# SimplePayload.net
KiCad netlist of a schematic drawn in EAGLE
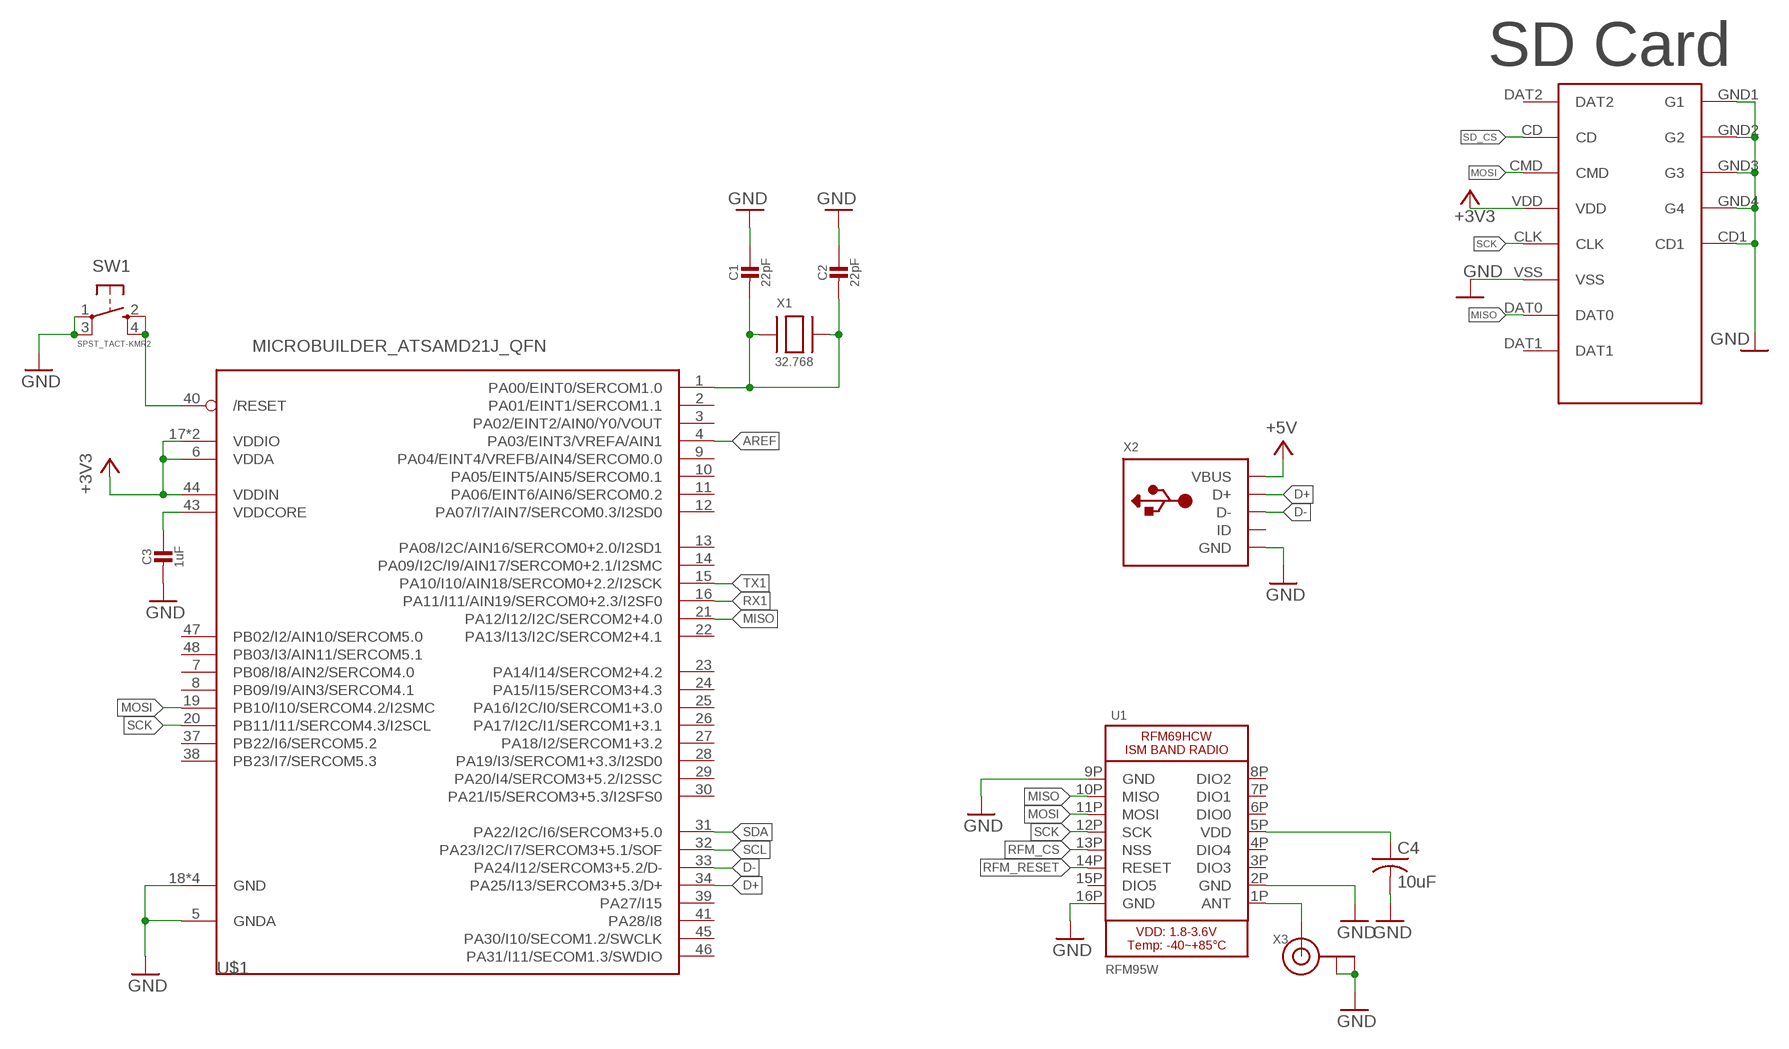
[diagram p0: schematic, sheet 1]

(export (version "E")
  (design (tool "Eeschema 10.0.6"))
  (components
    (comp (ref "C1")
      (value "22pF")
      (footprint "eagle-import:MICROBUILDER_0603-NO")
      (libsource (lib "eagle-import") (part "MICROBUILDER_CAP_CERAMIC0603_NO"))
    )
    (comp (ref "C2")
      (value "22pF")
      (footprint "eagle-import:MICROBUILDER_0603-NO")
      (libsource (lib "eagle-import") (part "MICROBUILDER_CAP_CERAMIC0603_NO"))
    )
    (comp (ref "C3")
      (value "1uF")
      (footprint "eagle-import:MICROBUILDER_0603-NO")
      (libsource (lib "eagle-import") (part "MICROBUILDER_CAP_CERAMIC0603_NO"))
    )
    (comp (ref "C4")
      (value "10uF")
      (footprint "eagle-import:C0805")
      (libsource (lib "eagle-import") (part "C-USC0805"))
    )
    (comp (ref "SW1")
      (value "SPST_TACT-KMR2")
      (footprint "eagle-import:KMR2")
      (libsource (lib "eagle-import") (part "SPST_TACT-KMR2"))
    )
    (comp (ref "U$1")
      (value "MICROBUILDER_ATSAMD21J_QFN")
      (footprint "eagle-import:MICROBUILDER_TQFN48_7MM")
      (libsource (lib "eagle-import") (part "MICROBUILDER_ATSAMD21J_QFN"))
    )
    (comp (ref "U$4")
      (value "MICRO_SD")
      (footprint "eagle-import:MICRO_SD_HINGED")
      (libsource (lib "eagle-import") (part "MICRO_SD"))
    )
    (comp (ref "U1")
      (value "RFM95W")
      (footprint "eagle-import:MICROBUILDER_RFMHCW_SMT")
      (libsource (lib "eagle-import") (part "MICROBUILDER_RFM69HCW_SMT"))
    )
    (comp (ref "X1")
      (value "32.768")
      (footprint "eagle-import:ADAFRUIT2_XTAL3215")
      (libsource (lib "eagle-import") (part "ADAFRUIT2_XTAL-3.2X1.5"))
    )
    (comp (ref "X2")
      (value "MICROBUILDER_USB_MICRO_20329_V2")
      (footprint "eagle-import:MICROBUILDER_4UCONN_20329_V2")
      (libsource (lib "eagle-import") (part "MICROBUILDER_USB_MICRO_20329_V2"))
    )
    (comp (ref "X3")
      (value "MICROBUILDER_ANTENNA_U.FL")
      (footprint "eagle-import:MICROBUILDER_U.FL")
      (libsource (lib "eagle-import") (part "MICROBUILDER_ANTENNA_U.FL"))
    )
  )
  (nets
    (net (code "1") (name "+3V3") (class "Default")
      (node (ref "U$1") (pin "17") (pinfunction "VDDIO_17") (pintype "power_in"))
      (node (ref "U$1") (pin "36") (pinfunction "VDDIO_36") (pintype "power_in"))
      (node (ref "U$1") (pin "44") (pinfunction "VDDIN_44") (pintype "power_in"))
      (node (ref "U$1") (pin "6") (pinfunction "VDDA_6") (pintype "power_in"))
      (node (ref "U$4") (pin "VDD") (pinfunction "VDD_VDD") (pintype "bidirectional"))
    )
    (net (code "2") (name "+5V") (class "Default")
      (node (ref "X2") (pin "VBUS") (pinfunction "VBUS_VBUS") (pintype "power_in"))
    )
    (net (code "3") (name "AREF") (class "Default")
      (node (ref "U$1") (pin "4") (pinfunction "PA03/EINT3/VREFA/AIN1_4") (pintype "bidirectional"))
    )
    (net (code "4") (name "D+") (class "Default")
      (node (ref "U$1") (pin "34") (pinfunction "PA25/I13/SERCOM3+5.3/D+_34") (pintype "bidirectional"))
      (node (ref "X2") (pin "D+") (pinfunction "D+_D+") (pintype "bidirectional"))
    )
    (net (code "5") (name "D-") (class "Default")
      (node (ref "U$1") (pin "33") (pinfunction "PA24/I12/SERCOM3+5.2/D-_33") (pintype "bidirectional"))
      (node (ref "X2") (pin "D-") (pinfunction "D-_D-") (pintype "bidirectional"))
    )
    (net (code "6") (name "GND") (class "Default")
      (node (ref "C1") (pin "1") (pinfunction "1_1") (pintype "passive"))
      (node (ref "C2") (pin "1") (pinfunction "1_1") (pintype "passive"))
      (node (ref "C3") (pin "2") (pinfunction "2_2") (pintype "passive"))
      (node (ref "C4") (pin "2") (pinfunction "2_2") (pintype "passive"))
      (node (ref "SW1") (pin "1") (pinfunction "P_1") (pintype "passive"))
      (node (ref "SW1") (pin "3") (pinfunction "P1_3") (pintype "passive"))
      (node (ref "U$1") (pin "18") (pinfunction "GND_18") (pintype "power_in"))
      (node (ref "U$1") (pin "35") (pinfunction "GND_35") (pintype "power_in"))
      (node (ref "U$1") (pin "42") (pinfunction "GND_42") (pintype "power_in"))
      (node (ref "U$1") (pin "5") (pinfunction "GNDA_5") (pintype "power_in"))
      (node (ref "U$1") (pin "THERMAL") (pinfunction "GND_THERMAL") (pintype "power_in"))
      (node (ref "U$4") (pin "CD1") (pinfunction "CD1_CD1") (pintype "bidirectional"))
      (node (ref "U$4") (pin "GND1") (pinfunction "G1_GND1") (pintype "bidirectional"))
      (node (ref "U$4") (pin "GND2") (pinfunction "G2_GND2") (pintype "bidirectional"))
      (node (ref "U$4") (pin "GND3") (pinfunction "G3_GND3") (pintype "bidirectional"))
      (node (ref "U$4") (pin "GND4") (pinfunction "G4_GND4") (pintype "bidirectional"))
      (node (ref "U$4") (pin "VSS") (pinfunction "VSS_VSS") (pintype "bidirectional"))
      (node (ref "U1") (pin "16P") (pinfunction "GND_16P") (pintype "power_in"))
      (node (ref "U1") (pin "2P") (pinfunction "GND_2P") (pintype "power_in"))
      (node (ref "U1") (pin "9P") (pinfunction "GND_9P") (pintype "power_in"))
      (node (ref "X2") (pin "BASE@1") (pinfunction "GND_BASE@1") (pintype "power_in"))
      (node (ref "X2") (pin "BASE@2") (pinfunction "GND_BASE@2") (pintype "power_in"))
      (node (ref "X2") (pin "GND") (pinfunction "GND_GND") (pintype "power_in"))
      (node (ref "X2") (pin "SPRT@1") (pinfunction "GND_SPRT@1") (pintype "power_in"))
      (node (ref "X2") (pin "SPRT@2") (pinfunction "GND_SPRT@2") (pintype "power_in"))
      (node (ref "X2") (pin "SPRT@3") (pinfunction "GND_SPRT@3") (pintype "power_in"))
      (node (ref "X2") (pin "SPRT@4") (pinfunction "GND_SPRT@4") (pintype "power_in"))
      (node (ref "X3") (pin "1") (pinfunction "GND_1") (pintype "passive"))
      (node (ref "X3") (pin "2") (pinfunction "GND_2") (pintype "passive"))
    )
    (net (code "7") (name "MISO") (class "Default")
      (node (ref "U$1") (pin "21") (pinfunction "PA12/I12/I2C/SERCOM2+4.0_21") (pintype "bidirectional"))
      (node (ref "U$4") (pin "DAT0") (pinfunction "DAT0_DAT0") (pintype "bidirectional"))
      (node (ref "U1") (pin "10P") (pinfunction "MISO_10P") (pintype "output"))
    )
    (net (code "8") (name "MOSI") (class "Default")
      (node (ref "U$1") (pin "19") (pinfunction "PB10/I10/SERCOM4.2/I2SMC_19") (pintype "bidirectional"))
      (node (ref "U$4") (pin "CMD") (pinfunction "CMD_CMD") (pintype "bidirectional"))
      (node (ref "U1") (pin "11P") (pinfunction "MOSI_11P") (pintype "input"))
    )
    (net (code "9") (name "Net-(SW1-S)") (class "Default")
      (node (ref "SW1") (pin "2") (pinfunction "S_2") (pintype "passive"))
      (node (ref "SW1") (pin "4") (pinfunction "S1_4") (pintype "passive"))
      (node (ref "U$1") (pin "40") (pinfunction "/RESET_40") (pintype "bidirectional"))
    )
    (net (code "10") (name "Net-(U$1-PA00{slash}EINT0{slash}SERCOM1.0)") (class "Default")
      (node (ref "C1") (pin "2") (pinfunction "2_2") (pintype "passive"))
      (node (ref "C2") (pin "2") (pinfunction "2_2") (pintype "passive"))
      (node (ref "U$1") (pin "1") (pinfunction "PA00/EINT0/SERCOM1.0_1") (pintype "bidirectional"))
      (node (ref "X1") (pin "P$1") (pinfunction "P$1_P$1") (pintype "bidirectional"))
      (node (ref "X1") (pin "P$2") (pinfunction "P$2_P$2") (pintype "bidirectional"))
    )
    (net (code "11") (name "Net-(U$1-VDDCORE)") (class "Default")
      (node (ref "C3") (pin "1") (pinfunction "1_1") (pintype "passive"))
      (node (ref "U$1") (pin "43") (pinfunction "VDDCORE_43") (pintype "power_in"))
    )
    (net (code "12") (name "Net-(U1-ANT)") (class "Default")
      (node (ref "U1") (pin "1P") (pinfunction "ANT_1P") (pintype "bidirectional"))
      (node (ref "X3") (pin "3") (pinfunction "SIGNAL_3") (pintype "passive"))
    )
    (net (code "13") (name "Net-(U1-VDD)") (class "Default")
      (node (ref "C4") (pin "1") (pinfunction "1_1") (pintype "passive"))
      (node (ref "U1") (pin "5P") (pinfunction "VDD_5P") (pintype "power_in"))
    )
    (net (code "14") (name "RFM_CS") (class "Default")
      (node (ref "U1") (pin "13P") (pinfunction "NSS_13P") (pintype "input"))
    )
    (net (code "15") (name "RFM_RESET") (class "Default")
      (node (ref "U1") (pin "14P") (pinfunction "RESET_14P") (pintype "input"))
    )
    (net (code "16") (name "RX1") (class "Default")
      (node (ref "U$1") (pin "16") (pinfunction "PA11/I11/AIN19/SERCOM0+2.3/I2SF0_16") (pintype "bidirectional"))
    )
    (net (code "17") (name "SCK") (class "Default")
      (node (ref "U$1") (pin "20") (pinfunction "PB11/I11/SERCOM4.3/I2SCL_20") (pintype "bidirectional"))
      (node (ref "U$4") (pin "CLK") (pinfunction "CLK_CLK") (pintype "bidirectional"))
      (node (ref "U1") (pin "12P") (pinfunction "SCK_12P") (pintype "input"))
    )
    (net (code "18") (name "SCL") (class "Default")
      (node (ref "U$1") (pin "32") (pinfunction "PA23/I2C/I7/SERCOM3+5.1/SOF_32") (pintype "bidirectional"))
    )
    (net (code "19") (name "SDA") (class "Default")
      (node (ref "U$1") (pin "31") (pinfunction "PA22/I2C/I6/SERCOM3+5.0_31") (pintype "bidirectional"))
    )
    (net (code "20") (name "SD_CS") (class "Default")
      (node (ref "U$4") (pin "CD") (pinfunction "CD_CD") (pintype "bidirectional"))
    )
    (net (code "21") (name "TX1") (class "Default")
      (node (ref "U$1") (pin "15") (pinfunction "PA10/I10/AIN18/SERCOM0+2.2/I2SCK_15") (pintype "bidirectional"))
    )
    (net (code "22") (name "unconnected-(U$1-PA01{slash}EINT1{slash}SERCOM1.1-Pad2)") (class "Default")
      (node (ref "U$1") (pin "2") (pinfunction "PA01/EINT1/SERCOM1.1_2") (pintype "bidirectional"))
    )
    (net (code "23") (name "unconnected-(U$1-PA02{slash}EINT2{slash}AIN0{slash}Y0{slash}VOUT-Pad3)") (class "Default")
      (node (ref "U$1") (pin "3") (pinfunction "PA02/EINT2/AIN0/Y0/VOUT_3") (pintype "bidirectional"))
    )
    (net (code "24") (name "unconnected-(U$1-PA04{slash}EINT4{slash}VREFB{slash}AIN4{slash}SERCOM0.0-Pad9)") (class "Default")
      (node (ref "U$1") (pin "9") (pinfunction "PA04/EINT4/VREFB/AIN4/SERCOM0.0_9") (pintype "bidirectional"))
    )
    (net (code "25") (name "unconnected-(U$1-PA05{slash}EINT5{slash}AIN5{slash}SERCOM0.1-Pad10)") (class "Default")
      (node (ref "U$1") (pin "10") (pinfunction "PA05/EINT5/AIN5/SERCOM0.1_10") (pintype "bidirectional"))
    )
    (net (code "26") (name "unconnected-(U$1-PA06{slash}EINT6{slash}AIN6{slash}SERCOM0.2-Pad11)") (class "Default")
      (node (ref "U$1") (pin "11") (pinfunction "PA06/EINT6/AIN6/SERCOM0.2_11") (pintype "bidirectional"))
    )
    (net (code "27") (name "unconnected-(U$1-PA07{slash}I7{slash}AIN7{slash}SERCOM0.3{slash}I2SD0-Pad12)") (class "Default")
      (node (ref "U$1") (pin "12") (pinfunction "PA07/I7/AIN7/SERCOM0.3/I2SD0_12") (pintype "bidirectional"))
    )
    (net (code "28") (name "unconnected-(U$1-PA08{slash}I2C{slash}AIN16{slash}SERCOM0+2.0{slash}I2SD1-Pad13)") (class "Default")
      (node (ref "U$1") (pin "13") (pinfunction "PA08/I2C/AIN16/SERCOM0+2.0/I2SD1_13") (pintype "bidirectional"))
    )
    (net (code "29") (name "unconnected-(U$1-PA09{slash}I2C{slash}I9{slash}AIN17{slash}SERCOM0+2.1{slash}I2SMC-Pad14)") (class "Default")
      (node (ref "U$1") (pin "14") (pinfunction "PA09/I2C/I9/AIN17/SERCOM0+2.1/I2SMC_14") (pintype "bidirectional"))
    )
    (net (code "30") (name "unconnected-(U$1-PA13{slash}I13{slash}I2C{slash}SERCOM2+4.1-Pad22)") (class "Default")
      (node (ref "U$1") (pin "22") (pinfunction "PA13/I13/I2C/SERCOM2+4.1_22") (pintype "bidirectional"))
    )
    (net (code "31") (name "unconnected-(U$1-PA14{slash}I14{slash}SERCOM2+4.2-Pad23)") (class "Default")
      (node (ref "U$1") (pin "23") (pinfunction "PA14/I14/SERCOM2+4.2_23") (pintype "bidirectional"))
    )
    (net (code "32") (name "unconnected-(U$1-PA15{slash}I15{slash}SERCOM3+4.3-Pad24)") (class "Default")
      (node (ref "U$1") (pin "24") (pinfunction "PA15/I15/SERCOM3+4.3_24") (pintype "bidirectional"))
    )
    (net (code "33") (name "unconnected-(U$1-PA16{slash}I2C{slash}I0{slash}SERCOM1+3.0-Pad25)") (class "Default")
      (node (ref "U$1") (pin "25") (pinfunction "PA16/I2C/I0/SERCOM1+3.0_25") (pintype "bidirectional"))
    )
    (net (code "34") (name "unconnected-(U$1-PA17{slash}I2C{slash}I1{slash}SERCOM1+3.1-Pad26)") (class "Default")
      (node (ref "U$1") (pin "26") (pinfunction "PA17/I2C/I1/SERCOM1+3.1_26") (pintype "bidirectional"))
    )
    (net (code "35") (name "unconnected-(U$1-PA18{slash}I2{slash}SERCOM1+3.2-Pad27)") (class "Default")
      (node (ref "U$1") (pin "27") (pinfunction "PA18/I2/SERCOM1+3.2_27") (pintype "bidirectional"))
    )
    (net (code "36") (name "unconnected-(U$1-PA19{slash}I3{slash}SERCOM1+3.3{slash}I2SD0-Pad28)") (class "Default")
      (node (ref "U$1") (pin "28") (pinfunction "PA19/I3/SERCOM1+3.3/I2SD0_28") (pintype "bidirectional"))
    )
    (net (code "37") (name "unconnected-(U$1-PA20{slash}I4{slash}SERCOM3+5.2{slash}I2SSC-Pad29)") (class "Default")
      (node (ref "U$1") (pin "29") (pinfunction "PA20/I4/SERCOM3+5.2/I2SSC_29") (pintype "bidirectional"))
    )
    (net (code "38") (name "unconnected-(U$1-PA21{slash}I5{slash}SERCOM3+5.3{slash}I2SFS0-Pad30)") (class "Default")
      (node (ref "U$1") (pin "30") (pinfunction "PA21/I5/SERCOM3+5.3/I2SFS0_30") (pintype "bidirectional"))
    )
    (net (code "39") (name "unconnected-(U$1-PA27{slash}I15-Pad39)") (class "Default")
      (node (ref "U$1") (pin "39") (pinfunction "PA27/I15_39") (pintype "bidirectional"))
    )
    (net (code "40") (name "unconnected-(U$1-PA28{slash}I8-Pad41)") (class "Default")
      (node (ref "U$1") (pin "41") (pinfunction "PA28/I8_41") (pintype "bidirectional"))
    )
    (net (code "41") (name "unconnected-(U$1-PA30{slash}I10{slash}SECOM1.2{slash}SWCLK-Pad45)") (class "Default")
      (node (ref "U$1") (pin "45") (pinfunction "PA30/I10/SECOM1.2/SWCLK_45") (pintype "bidirectional"))
    )
    (net (code "42") (name "unconnected-(U$1-PA31{slash}I11{slash}SECOM1.3{slash}SWDIO-Pad46)") (class "Default")
      (node (ref "U$1") (pin "46") (pinfunction "PA31/I11/SECOM1.3/SWDIO_46") (pintype "bidirectional"))
    )
    (net (code "43") (name "unconnected-(U$1-PB02{slash}I2{slash}AIN10{slash}SERCOM5.0-Pad47)") (class "Default")
      (node (ref "U$1") (pin "47") (pinfunction "PB02/I2/AIN10/SERCOM5.0_47") (pintype "bidirectional"))
    )
    (net (code "44") (name "unconnected-(U$1-PB03{slash}I3{slash}AIN11{slash}SERCOM5.1-Pad48)") (class "Default")
      (node (ref "U$1") (pin "48") (pinfunction "PB03/I3/AIN11/SERCOM5.1_48") (pintype "bidirectional"))
    )
    (net (code "45") (name "unconnected-(U$1-PB08{slash}I8{slash}AIN2{slash}SERCOM4.0-Pad7)") (class "Default")
      (node (ref "U$1") (pin "7") (pinfunction "PB08/I8/AIN2/SERCOM4.0_7") (pintype "bidirectional"))
    )
    (net (code "46") (name "unconnected-(U$1-PB09{slash}I9{slash}AIN3{slash}SERCOM4.1-Pad8)") (class "Default")
      (node (ref "U$1") (pin "8") (pinfunction "PB09/I9/AIN3/SERCOM4.1_8") (pintype "bidirectional"))
    )
    (net (code "47") (name "unconnected-(U$1-PB22{slash}I6{slash}SERCOM5.2-Pad37)") (class "Default")
      (node (ref "U$1") (pin "37") (pinfunction "PB22/I6/SERCOM5.2_37") (pintype "bidirectional"))
    )
    (net (code "48") (name "unconnected-(U$1-PB23{slash}I7{slash}SERCOM5.3-Pad38)") (class "Default")
      (node (ref "U$1") (pin "38") (pinfunction "PB23/I7/SERCOM5.3_38") (pintype "bidirectional"))
    )
    (net (code "49") (name "unconnected-(U$4-PadDAT1)") (class "Default")
      (node (ref "U$4") (pin "DAT1") (pinfunction "DAT1_DAT1") (pintype "bidirectional"))
    )
    (net (code "50") (name "unconnected-(U$4-PadDAT2)") (class "Default")
      (node (ref "U$4") (pin "DAT2") (pinfunction "DAT2_DAT2") (pintype "bidirectional"))
    )
    (net (code "51") (name "unconnected-(U1-DIO0-Pad6P)") (class "Default")
      (node (ref "U1") (pin "6P") (pinfunction "DIO0_6P") (pintype "bidirectional"))
    )
    (net (code "52") (name "unconnected-(U1-DIO1-Pad7P)") (class "Default")
      (node (ref "U1") (pin "7P") (pinfunction "DIO1_7P") (pintype "bidirectional"))
    )
    (net (code "53") (name "unconnected-(U1-DIO2-Pad8P)") (class "Default")
      (node (ref "U1") (pin "8P") (pinfunction "DIO2_8P") (pintype "bidirectional"))
    )
    (net (code "54") (name "unconnected-(U1-DIO3-Pad3P)") (class "Default")
      (node (ref "U1") (pin "3P") (pinfunction "DIO3_3P") (pintype "bidirectional"))
    )
    (net (code "55") (name "unconnected-(U1-DIO4-Pad4P)") (class "Default")
      (node (ref "U1") (pin "4P") (pinfunction "DIO4_4P") (pintype "bidirectional"))
    )
    (net (code "56") (name "unconnected-(U1-DIO5-Pad15P)") (class "Default")
      (node (ref "U1") (pin "15P") (pinfunction "DIO5_15P") (pintype "bidirectional"))
    )
    (net (code "57") (name "unconnected-(X2-PadID)") (class "Default")
      (node (ref "X2") (pin "ID") (pinfunction "ID_ID") (pintype "bidirectional"))
    )
  )
)
